# dice-2.net
KiCad netlist of a schematic drawn in EAGLE
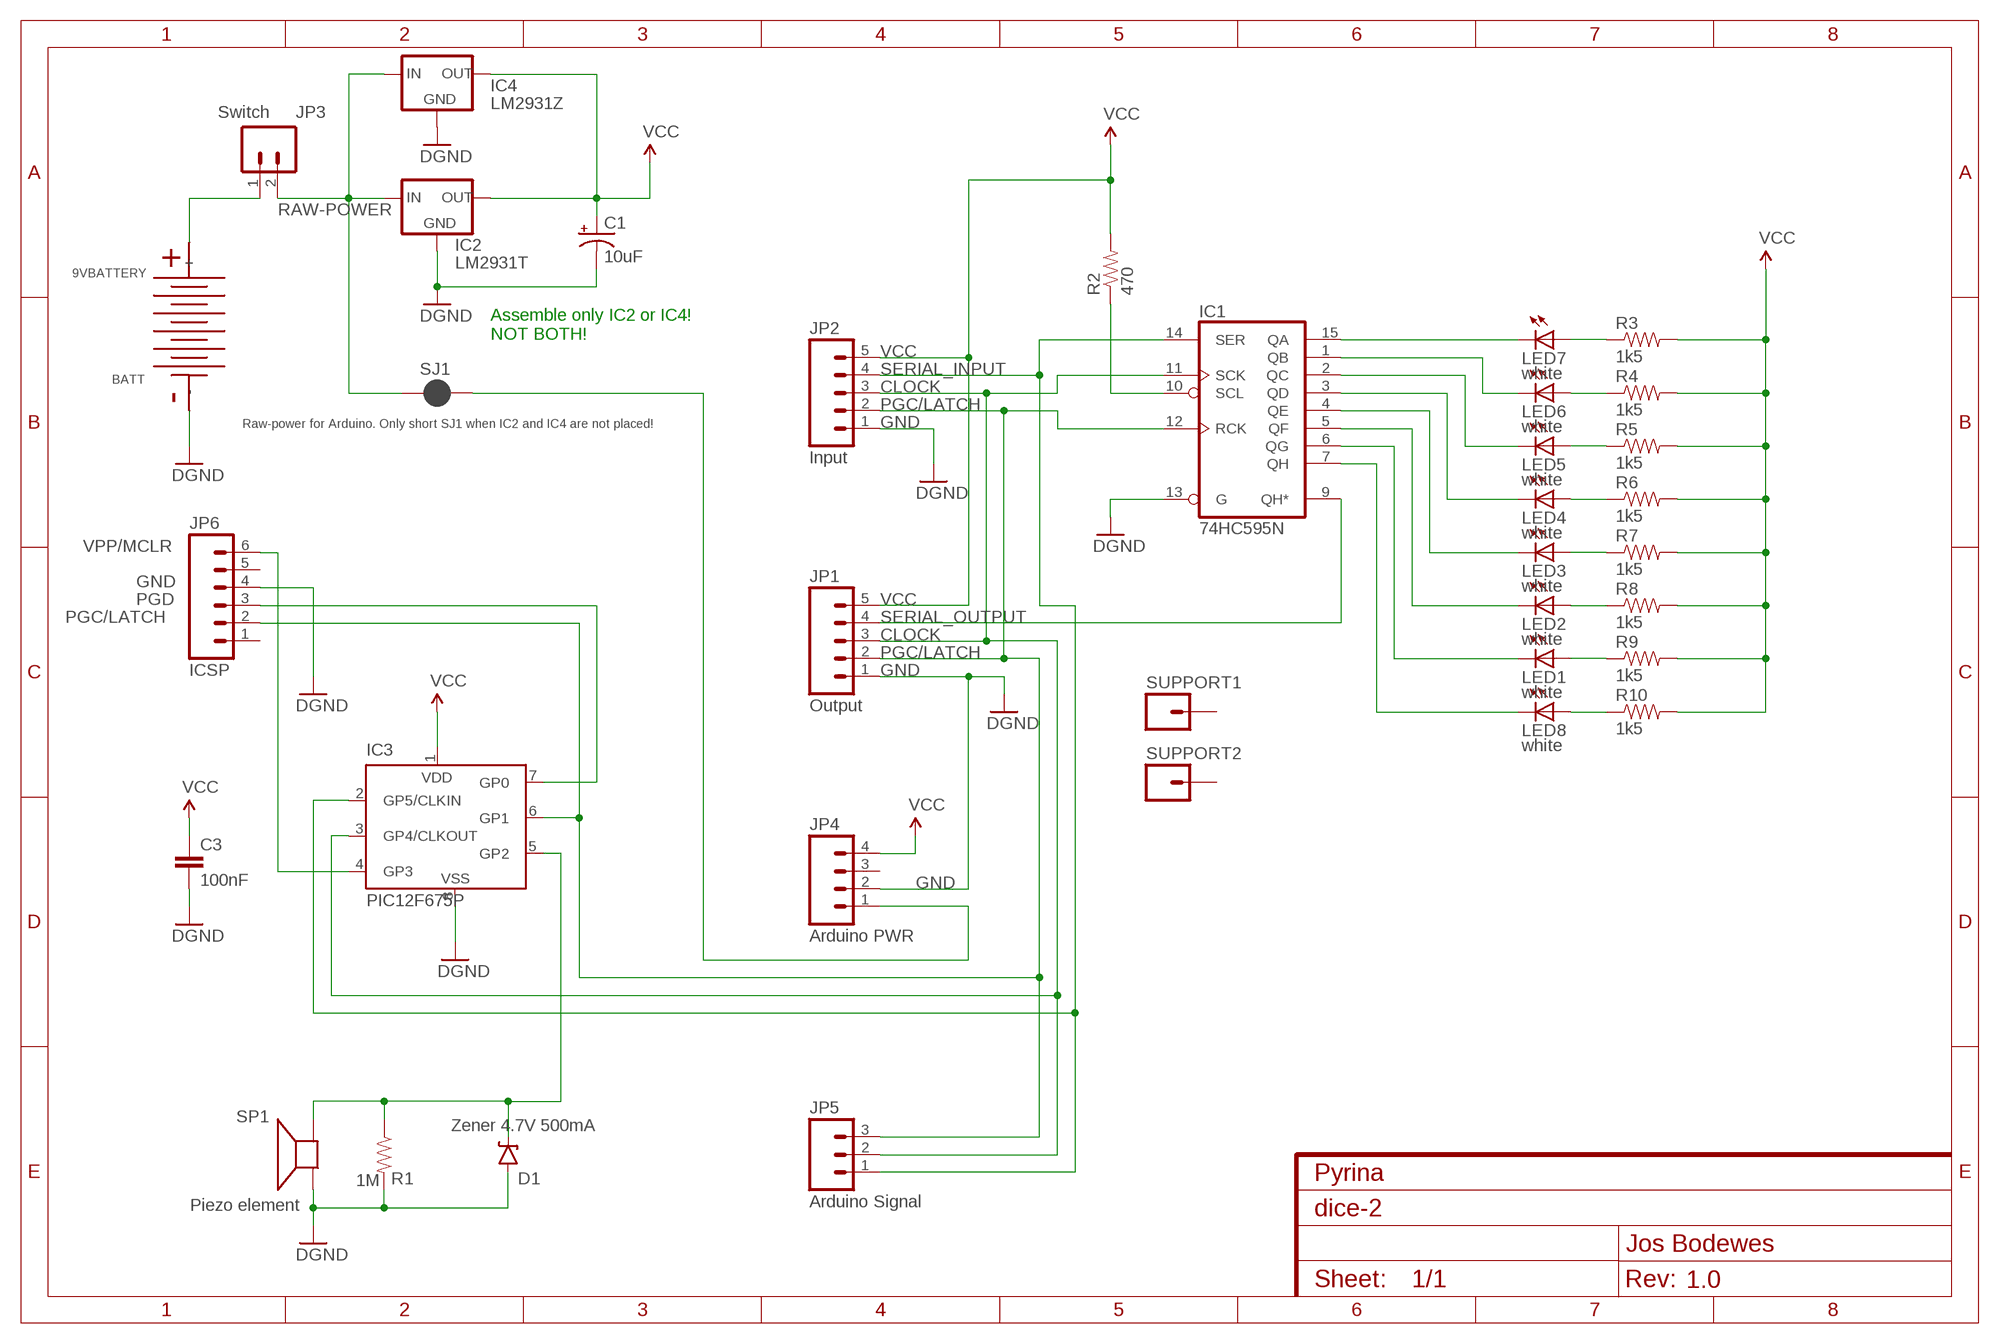
[diagram p0: schematic, sheet 1]

(export (version "E")
  (design (tool "Eeschema 10.0.6"))
  (components
    (comp (ref "BATT")
      (value "9VBATTERY")
      (footprint "eagle-import:9V-BATTERY-HOLDER")
      (libsource (lib "eagle-import") (part "9VBATTERY"))
    )
    (comp (ref "C1")
      (value "10uF")
      (footprint "eagle-import:CPOL-RADIAL-10UF-25V")
      (libsource (lib "eagle-import") (part "CAP_POLPTH2"))
    )
    (comp (ref "C3")
      (value "100nF")
      (footprint "eagle-import:CAP-PTH-5MM")
      (libsource (lib "eagle-import") (part "CAPPTH1"))
    )
    (comp (ref "D1")
      (value "Zener 4.7V 500mA")
      (footprint "eagle-import:DIODE-ZENER")
      (libsource (lib "eagle-import") (part "DIODE-ZENERPTH"))
    )
    (comp (ref "IC1")
      (value "74HC595N")
      (footprint "eagle-import:DIL16")
      (libsource (lib "eagle-import") (part "74595NHC"))
    )
    (comp (ref "IC2")
      (value "LM2931T")
      (footprint "eagle-import:TO220S")
      (libsource (lib "eagle-import") (part "LM2931T"))
    )
    (comp (ref "IC3")
      (value "PIC12F675P")
      (footprint "eagle-import:DIL8")
      (fields (field (name "MF") "MICROCHIP") (field (name "MPN") "PIC12F675-E/P"))
      (libsource (lib "eagle-import") (part "PIC12F6P75"))
    )
    (comp (ref "IC4")
      (value "LM2931Z")
      (footprint "eagle-import:TO92")
      (libsource (lib "eagle-import") (part "LM2931Z"))
    )
    (comp (ref "JP1")
      (value "Output")
      (footprint "eagle-import:1X05")
      (libsource (lib "eagle-import") (part "M05PTH"))
    )
    (comp (ref "JP2")
      (value "Input")
      (footprint "eagle-import:1X05")
      (libsource (lib "eagle-import") (part "M05PTH"))
    )
    (comp (ref "JP3")
      (value "Switch")
      (footprint "eagle-import:1X02")
      (libsource (lib "eagle-import") (part "M02PTH"))
    )
    (comp (ref "JP4")
      (value "Arduino PWR")
      (footprint "eagle-import:1X04")
      (libsource (lib "eagle-import") (part "M04PTH"))
    )
    (comp (ref "JP5")
      (value "Arduino Signal")
      (footprint "eagle-import:1X03")
      (libsource (lib "eagle-import") (part "M03PTH"))
    )
    (comp (ref "JP6")
      (value "ICSP")
      (footprint "eagle-import:1X06-SIP_LOCK")
      (libsource (lib "eagle-import") (part "M06SIP_LOCK"))
    )
    (comp (ref "LED1")
      (value "white")
      (footprint "eagle-import:LED5MM")
      (libsource (lib "eagle-import") (part "LED5MM"))
    )
    (comp (ref "LED2")
      (value "white")
      (footprint "eagle-import:LED5MM")
      (libsource (lib "eagle-import") (part "LED5MM"))
    )
    (comp (ref "LED3")
      (value "white")
      (footprint "eagle-import:LED5MM")
      (libsource (lib "eagle-import") (part "LED5MM"))
    )
    (comp (ref "LED4")
      (value "white")
      (footprint "eagle-import:LED5MM")
      (libsource (lib "eagle-import") (part "LED5MM"))
    )
    (comp (ref "LED5")
      (value "white")
      (footprint "eagle-import:LED5MM")
      (libsource (lib "eagle-import") (part "LED5MM"))
    )
    (comp (ref "LED6")
      (value "white")
      (footprint "eagle-import:LED5MM")
      (libsource (lib "eagle-import") (part "LED5MM"))
    )
    (comp (ref "LED7")
      (value "white")
      (footprint "eagle-import:LED5MM")
      (libsource (lib "eagle-import") (part "LED5MM"))
    )
    (comp (ref "LED8")
      (value "white")
      (footprint "eagle-import:LED5MM")
      (libsource (lib "eagle-import") (part "LED5MM"))
    )
    (comp (ref "R1")
      (value "1M")
      (footprint "eagle-import:AXIAL-0.4")
      (libsource (lib "eagle-import") (part "RESISTORPTH-1/4W"))
    )
    (comp (ref "R2")
      (value "470")
      (footprint "eagle-import:AXIAL-0.4")
      (libsource (lib "eagle-import") (part "RESISTORPTH-1/4W"))
    )
    (comp (ref "R3")
      (value "1k5")
      (footprint "eagle-import:AXIAL-0.4")
      (libsource (lib "eagle-import") (part "RESISTORPTH-1/4W"))
    )
    (comp (ref "R4")
      (value "1k5")
      (footprint "eagle-import:AXIAL-0.4")
      (libsource (lib "eagle-import") (part "RESISTORPTH-1/4W"))
    )
    (comp (ref "R5")
      (value "1k5")
      (footprint "eagle-import:AXIAL-0.4")
      (libsource (lib "eagle-import") (part "RESISTORPTH-1/4W"))
    )
    (comp (ref "R6")
      (value "1k5")
      (footprint "eagle-import:AXIAL-0.4")
      (libsource (lib "eagle-import") (part "RESISTORPTH-1/4W"))
    )
    (comp (ref "R7")
      (value "1k5")
      (footprint "eagle-import:AXIAL-0.4")
      (libsource (lib "eagle-import") (part "RESISTORPTH-1/4W"))
    )
    (comp (ref "R8")
      (value "1k5")
      (footprint "eagle-import:AXIAL-0.4")
      (libsource (lib "eagle-import") (part "RESISTORPTH-1/4W"))
    )
    (comp (ref "R9")
      (value "1k5")
      (footprint "eagle-import:AXIAL-0.4")
      (libsource (lib "eagle-import") (part "RESISTORPTH-1/4W"))
    )
    (comp (ref "R10")
      (value "1k5")
      (footprint "eagle-import:AXIAL-0.4")
      (libsource (lib "eagle-import") (part "RESISTORPTH-1/4W"))
    )
    (comp (ref "SJ1")
      (value "Raw-power for Arduino. Only short SJ1 when IC2 and IC4 are not placed!")
      (footprint "eagle-import:PAD-JUMPER-2-NC_BY_PASTE_YES_SILK")
      (libsource (lib "eagle-import") (part "JUMPER-PAD-2-NC_BY_PASTE"))
    )
    (comp (ref "SP1")
      (value "Piezo element")
      (footprint "eagle-import:PS12")
      (libsource (lib "eagle-import") (part "SPEAKER/PS12"))
    )
    (comp (ref "SUPPORT1")
      (value "M01PTH")
      (footprint "eagle-import:1X01")
      (libsource (lib "eagle-import") (part "M01PTH"))
    )
    (comp (ref "SUPPORT2")
      (value "M01PTH")
      (footprint "eagle-import:1X01")
      (libsource (lib "eagle-import") (part "M01PTH"))
    )
  )
  (nets
    (net (code "1") (name "/CLOCK") (class "Default")
      (node (ref "IC1") (pin "11") (pinfunction "SCK_11") (pintype "input"))
      (node (ref "IC3") (pin "3") (pinfunction "GP4/CLKOUT_3") (pintype "bidirectional"))
      (node (ref "JP1") (pin "3") (pinfunction "3_3") (pintype "passive"))
      (node (ref "JP2") (pin "3") (pinfunction "3_3") (pintype "passive"))
      (node (ref "JP5") (pin "2") (pinfunction "2_2") (pintype "passive"))
    )
    (net (code "2") (name "/PGC{slash}LATCH") (class "Default")
      (node (ref "IC1") (pin "12") (pinfunction "RCK_12") (pintype "input"))
      (node (ref "IC3") (pin "6") (pinfunction "GP1_6") (pintype "bidirectional"))
      (node (ref "JP1") (pin "2") (pinfunction "2_2") (pintype "passive"))
      (node (ref "JP2") (pin "2") (pinfunction "2_2") (pintype "passive"))
      (node (ref "JP5") (pin "3") (pinfunction "3_3") (pintype "passive"))
      (node (ref "JP6") (pin "2") (pinfunction "2_2") (pintype "passive"))
    )
    (net (code "3") (name "/PGD") (class "Default")
      (node (ref "IC3") (pin "7") (pinfunction "GP0_7") (pintype "bidirectional"))
      (node (ref "JP6") (pin "3") (pinfunction "3_3") (pintype "passive"))
    )
    (net (code "4") (name "/RAW-POWER") (class "Default")
      (node (ref "IC2") (pin "1") (pinfunction "IN_1") (pintype "input"))
      (node (ref "IC4") (pin "3") (pinfunction "IN_3") (pintype "input"))
      (node (ref "JP3") (pin "2") (pinfunction "2_2") (pintype "passive"))
      (node (ref "SJ1") (pin "1") (pinfunction "1_1") (pintype "passive"))
    )
    (net (code "5") (name "/SERIAL_INPUT") (class "Default")
      (node (ref "IC1") (pin "14") (pinfunction "SER_14") (pintype "input"))
      (node (ref "IC3") (pin "2") (pinfunction "GP5/CLKIN_2") (pintype "bidirectional"))
      (node (ref "JP2") (pin "4") (pinfunction "4_4") (pintype "passive"))
      (node (ref "JP5") (pin "1") (pinfunction "1_1") (pintype "passive"))
    )
    (net (code "6") (name "/SERIAL_OUTPUT") (class "Default")
      (node (ref "IC1") (pin "9") (pinfunction "QH*_9") (pintype "tri_state"))
      (node (ref "JP1") (pin "4") (pinfunction "4_4") (pintype "passive"))
    )
    (net (code "7") (name "/VPP{slash}MCLR") (class "Default")
      (node (ref "IC3") (pin "4") (pinfunction "GP3_4") (pintype "input"))
      (node (ref "JP6") (pin "6") (pinfunction "6_6") (pintype "passive"))
    )
    (net (code "8") (name "DGND") (class "Default")
      (node (ref "BATT") (pin "-") (pinfunction "-_-") (pintype "power_in"))
      (node (ref "C1") (pin "2") (pinfunction "-_2") (pintype "passive"))
      (node (ref "C3") (pin "2") (pinfunction "2_2") (pintype "passive"))
      (node (ref "D1") (pin "P$2") (pinfunction "A_P$2") (pintype "passive"))
      (node (ref "IC1") (pin "13") (pinfunction "G_13") (pintype "input"))
      (node (ref "IC2") (pin "2") (pinfunction "GND_2") (pintype "input"))
      (node (ref "IC3") (pin "8") (pinfunction "VSS_8") (pintype "power_in"))
      (node (ref "IC4") (pin "2") (pinfunction "GND_2") (pintype "input"))
      (node (ref "JP1") (pin "1") (pinfunction "1_1") (pintype "passive"))
      (node (ref "JP2") (pin "1") (pinfunction "1_1") (pintype "passive"))
      (node (ref "JP4") (pin "2") (pinfunction "2_2") (pintype "passive"))
      (node (ref "JP6") (pin "4") (pinfunction "4_4") (pintype "passive"))
      (node (ref "R1") (pin "P$2") (pinfunction "2_P$2") (pintype "passive"))
      (node (ref "SP1") (pin "P$1") (pinfunction "+_P$1") (pintype "passive"))
    )
    (net (code "9") (name "Net-(BATT-Pad+)") (class "Default")
      (node (ref "BATT") (pin "+") (pinfunction "+_+") (pintype "power_in"))
      (node (ref "JP3") (pin "1") (pinfunction "1_1") (pintype "passive"))
    )
    (net (code "10") (name "Net-(D1-C)") (class "Default")
      (node (ref "D1") (pin "P$1") (pinfunction "C_P$1") (pintype "passive"))
      (node (ref "IC3") (pin "5") (pinfunction "GP2_5") (pintype "bidirectional"))
      (node (ref "R1") (pin "P$1") (pinfunction "1_P$1") (pintype "passive"))
      (node (ref "SP1") (pin "P$2") (pinfunction "-_P$2") (pintype "passive"))
    )
    (net (code "11") (name "Net-(IC1A-QA)") (class "Default")
      (node (ref "IC1") (pin "15") (pinfunction "QA_15") (pintype "tri_state"))
      (node (ref "LED7") (pin "K") (pinfunction "C_K") (pintype "passive"))
    )
    (net (code "12") (name "Net-(IC1A-QB)") (class "Default")
      (node (ref "IC1") (pin "1") (pinfunction "QB_1") (pintype "tri_state"))
      (node (ref "LED6") (pin "K") (pinfunction "C_K") (pintype "passive"))
    )
    (net (code "13") (name "Net-(IC1A-QC)") (class "Default")
      (node (ref "IC1") (pin "2") (pinfunction "QC_2") (pintype "tri_state"))
      (node (ref "LED5") (pin "K") (pinfunction "C_K") (pintype "passive"))
    )
    (net (code "14") (name "Net-(IC1A-QD)") (class "Default")
      (node (ref "IC1") (pin "3") (pinfunction "QD_3") (pintype "tri_state"))
      (node (ref "LED4") (pin "K") (pinfunction "C_K") (pintype "passive"))
    )
    (net (code "15") (name "Net-(IC1A-QE)") (class "Default")
      (node (ref "IC1") (pin "4") (pinfunction "QE_4") (pintype "tri_state"))
      (node (ref "LED3") (pin "K") (pinfunction "C_K") (pintype "passive"))
    )
    (net (code "16") (name "Net-(IC1A-QF)") (class "Default")
      (node (ref "IC1") (pin "5") (pinfunction "QF_5") (pintype "tri_state"))
      (node (ref "LED2") (pin "K") (pinfunction "C_K") (pintype "passive"))
    )
    (net (code "17") (name "Net-(IC1A-QG)") (class "Default")
      (node (ref "IC1") (pin "6") (pinfunction "QG_6") (pintype "tri_state"))
      (node (ref "LED1") (pin "K") (pinfunction "C_K") (pintype "passive"))
    )
    (net (code "18") (name "Net-(IC1A-QH)") (class "Default")
      (node (ref "IC1") (pin "7") (pinfunction "QH_7") (pintype "tri_state"))
      (node (ref "LED8") (pin "K") (pinfunction "C_K") (pintype "passive"))
    )
    (net (code "19") (name "Net-(IC1A-SCL)") (class "Default")
      (node (ref "IC1") (pin "10") (pinfunction "SCL_10") (pintype "input"))
      (node (ref "R2") (pin "P$1") (pinfunction "1_P$1") (pintype "passive"))
    )
    (net (code "20") (name "Net-(JP4-Pad1)") (class "Default")
      (node (ref "JP4") (pin "1") (pinfunction "1_1") (pintype "passive"))
      (node (ref "SJ1") (pin "2") (pinfunction "2_2") (pintype "passive"))
    )
    (net (code "21") (name "Net-(R3-1)") (class "Default")
      (node (ref "LED7") (pin "A") (pinfunction "A_A") (pintype "passive"))
      (node (ref "R3") (pin "P$1") (pinfunction "1_P$1") (pintype "passive"))
    )
    (net (code "22") (name "Net-(R4-1)") (class "Default")
      (node (ref "LED6") (pin "A") (pinfunction "A_A") (pintype "passive"))
      (node (ref "R4") (pin "P$1") (pinfunction "1_P$1") (pintype "passive"))
    )
    (net (code "23") (name "Net-(R5-1)") (class "Default")
      (node (ref "LED5") (pin "A") (pinfunction "A_A") (pintype "passive"))
      (node (ref "R5") (pin "P$1") (pinfunction "1_P$1") (pintype "passive"))
    )
    (net (code "24") (name "Net-(R6-1)") (class "Default")
      (node (ref "LED4") (pin "A") (pinfunction "A_A") (pintype "passive"))
      (node (ref "R6") (pin "P$1") (pinfunction "1_P$1") (pintype "passive"))
    )
    (net (code "25") (name "Net-(R7-1)") (class "Default")
      (node (ref "LED3") (pin "A") (pinfunction "A_A") (pintype "passive"))
      (node (ref "R7") (pin "P$1") (pinfunction "1_P$1") (pintype "passive"))
    )
    (net (code "26") (name "Net-(R8-1)") (class "Default")
      (node (ref "LED2") (pin "A") (pinfunction "A_A") (pintype "passive"))
      (node (ref "R8") (pin "P$1") (pinfunction "1_P$1") (pintype "passive"))
    )
    (net (code "27") (name "Net-(R9-1)") (class "Default")
      (node (ref "LED1") (pin "A") (pinfunction "A_A") (pintype "passive"))
      (node (ref "R9") (pin "P$1") (pinfunction "1_P$1") (pintype "passive"))
    )
    (net (code "28") (name "Net-(R10-1)") (class "Default")
      (node (ref "LED8") (pin "A") (pinfunction "A_A") (pintype "passive"))
      (node (ref "R10") (pin "P$1") (pinfunction "1_P$1") (pintype "passive"))
    )
    (net (code "29") (name "VCC") (class "Default")
      (node (ref "C1") (pin "1") (pinfunction "+_1") (pintype "passive"))
      (node (ref "C3") (pin "1") (pinfunction "1_1") (pintype "passive"))
      (node (ref "IC2") (pin "3") (pinfunction "OUT_3") (pintype "passive"))
      (node (ref "IC3") (pin "1") (pinfunction "VDD_1") (pintype "power_in"))
      (node (ref "IC4") (pin "1") (pinfunction "OUT_1") (pintype "passive"))
      (node (ref "JP1") (pin "5") (pinfunction "5_5") (pintype "passive"))
      (node (ref "JP2") (pin "5") (pinfunction "5_5") (pintype "passive"))
      (node (ref "JP4") (pin "4") (pinfunction "4_4") (pintype "passive"))
      (node (ref "R10") (pin "P$2") (pinfunction "2_P$2") (pintype "passive"))
      (node (ref "R2") (pin "P$2") (pinfunction "2_P$2") (pintype "passive"))
      (node (ref "R3") (pin "P$2") (pinfunction "2_P$2") (pintype "passive"))
      (node (ref "R4") (pin "P$2") (pinfunction "2_P$2") (pintype "passive"))
      (node (ref "R5") (pin "P$2") (pinfunction "2_P$2") (pintype "passive"))
      (node (ref "R6") (pin "P$2") (pinfunction "2_P$2") (pintype "passive"))
      (node (ref "R7") (pin "P$2") (pinfunction "2_P$2") (pintype "passive"))
      (node (ref "R8") (pin "P$2") (pinfunction "2_P$2") (pintype "passive"))
      (node (ref "R9") (pin "P$2") (pinfunction "2_P$2") (pintype "passive"))
    )
    (net (code "30") (name "unconnected-(JP4-Pad3)") (class "Default")
      (node (ref "JP4") (pin "3") (pinfunction "3_3") (pintype "passive"))
    )
    (net (code "31") (name "unconnected-(JP6-Pad1)") (class "Default")
      (node (ref "JP6") (pin "1") (pinfunction "1_1") (pintype "passive"))
    )
    (net (code "32") (name "unconnected-(JP6-Pad5)") (class "Default")
      (node (ref "JP6") (pin "5") (pinfunction "5_5") (pintype "passive"))
    )
    (net (code "33") (name "unconnected-(SUPPORT1-Pad1)") (class "Default")
      (node (ref "SUPPORT1") (pin "1") (pinfunction "1_1") (pintype "passive"))
    )
    (net (code "34") (name "unconnected-(SUPPORT2-Pad1)") (class "Default")
      (node (ref "SUPPORT2") (pin "1") (pinfunction "1_1") (pintype "passive"))
    )
  )
)
